# EPS_SCH.net
KiCad netlist of a schematic drawn in Altium Designer
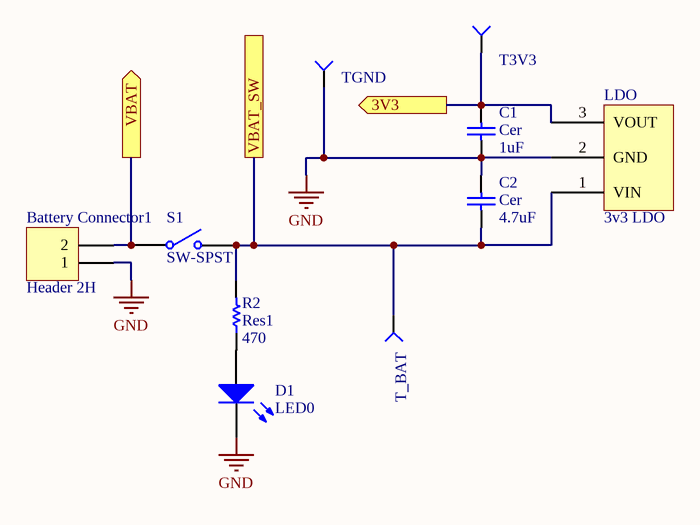
[diagram p0: EPS_SCH.SchDoc]

(export (version "E")
  (design (tool "Eeschema 10.0.6"))
  (components
    (comp (ref "Battery Connector1")
      (value "Header 2H")
      (footprint "BAT")
      (description "Header, 2-Pin, Right Angle")
      (fields (field (name "PUBLISHER") "Altium Limited"))
      (libsource (lib "Miscellaneous Connectors") (part "Header 2H"))
    )
    (comp (ref "C1")
      (value "Cer")
      (footprint "1608[0603]")
      (description "Capacitor")
      (fields (field (name "ALTIUM_VALUE") "1uF") (field (name "PUBLISHER") "Altium Limited"))
      (libsource (lib "Miscellaneous Devices") (part "Cap"))
    )
    (comp (ref "C2")
      (value "Cer")
      (footprint "1608[0603]")
      (description "Capacitor")
      (fields (field (name "ALTIUM_VALUE") "4.7uF") (field (name "PUBLISHER") "Altium Limited"))
      (libsource (lib "Miscellaneous Devices") (part "Cap"))
    )
    (comp (ref "D1")
      (value "LED0")
      (footprint "J1-0603")
      (description "Typical INFRARED GaAs LED")
      (fields (field (name "PUBLISHER") "Altium Limited"))
      (libsource (lib "Miscellaneous Devices") (part "LED0"))
    )
    (comp (ref "LDO")
      (value "3v3 LDO")
      (footprint "3V3LDO")
      (description "MCP1826S-3302E/AB")
      (libsource (lib "ATACS_SCH_LIB") (part "3v3 LDO"))
    )
    (comp (ref "R2")
      (value "Res1")
      (footprint "J1-0603")
      (description "Resistor")
      (fields (field (name "ALTIUM_VALUE") "470") (field (name "PUBLISHER") "Altium Limited"))
      (libsource (lib "Miscellaneous Devices") (part "Res1"))
    )
    (comp (ref "S1")
      (value "SW-SPST")
      (footprint "Switch")
      (description "Single-Pole, Single-Throw Switch")
      (fields (field (name "PUBLISHER") "Altium Limited"))
      (libsource (lib "Miscellaneous Devices") (part "SW-SPST"))
    )
    (comp (ref "T3V3")
      (value "Testpoint")
      (footprint "TESTPOINT")
      (description "Probe point for testing")
      (libsource (lib "MXLab Generic") (part "Testpoint"))
    )
    (comp (ref "TGND")
      (value "Testpoint")
      (footprint "TESTPOINT")
      (description "Probe point for testing")
      (libsource (lib "MXLab Generic") (part "Testpoint"))
    )
    (comp (ref "T_BAT")
      (value "Testpoint")
      (footprint "TESTPOINT")
      (description "Probe point for testing")
      (libsource (lib "MXLab Generic") (part "Testpoint"))
    )
  )
  (nets
    (net (code "1") (name "/3V3") (class "Default")
      (node (ref "C1") (pin "2") (pinfunction "2_2") (pintype "passive"))
      (node (ref "LDO") (pin "3") (pinfunction "VOUT_3") (pintype "passive"))
      (node (ref "T3V3") (pin "1") (pinfunction "1_1") (pintype "passive"))
    )
    (net (code "2") (name "/VBAT") (class "Default")
      (node (ref "Battery Connector1") (pin "2") (pinfunction "2_2") (pintype "passive"))
      (node (ref "S1") (pin "1") (pinfunction "COMMON_1") (pintype "passive"))
    )
    (net (code "3") (name "/VBAT_SW") (class "Default")
      (node (ref "C2") (pin "1") (pinfunction "1_1") (pintype "passive"))
      (node (ref "LDO") (pin "1") (pinfunction "VIN_1") (pintype "power_in"))
      (node (ref "R2") (pin "2") (pinfunction "2_2") (pintype "passive"))
      (node (ref "S1") (pin "2") (pinfunction "NO_2") (pintype "passive"))
      (node (ref "T_BAT") (pin "1") (pinfunction "1_1") (pintype "passive"))
    )
    (net (code "4") (name "GND") (class "Default")
      (node (ref "Battery Connector1") (pin "1") (pinfunction "1_1") (pintype "passive"))
      (node (ref "C1") (pin "1") (pinfunction "1_1") (pintype "passive"))
      (node (ref "C2") (pin "2") (pinfunction "2_2") (pintype "passive"))
      (node (ref "D1") (pin "2") (pinfunction "K_2") (pintype "passive"))
      (node (ref "LDO") (pin "2") (pinfunction "GND_2") (pintype "power_in"))
      (node (ref "TGND") (pin "1") (pinfunction "1_1") (pintype "passive"))
    )
    (net (code "5") (name "Net-(D1-A)") (class "Default")
      (node (ref "D1") (pin "1") (pinfunction "A_1") (pintype "passive"))
      (node (ref "R2") (pin "1") (pinfunction "1_1") (pintype "passive"))
    )
  )
)
